# lightampSMT.net
KiCad netlist of a schematic drawn in EAGLE
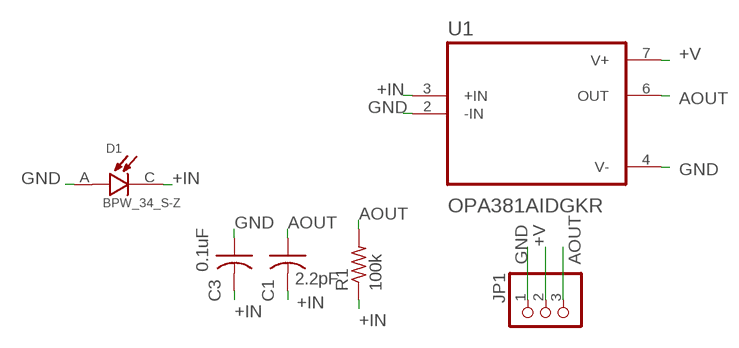
[diagram p0: schematic, sheet 1]

(export (version "E")
  (design (tool "Eeschema 10.0.6"))
  (components
    (comp (ref "C1")
      (value "2.2pF")
      (footprint "eagle-import:C0603K")
      (libsource (lib "eagle-import") (part "C-USC0603K"))
    )
    (comp (ref "C3")
      (value "0.1uF")
      (footprint "eagle-import:C0603K")
      (libsource (lib "eagle-import") (part "C-USC0603K"))
    )
    (comp (ref "D1")
      (value "BPW_34_S-Z")
      (footprint "eagle-import:DIO_BPW_34_S-Z")
      (fields (field (name "MF") "OSRAM Opto") (field (name "MP") "BPW 34 S-Z"))
      (libsource (lib "eagle-import") (part "BPW_34_S-Z"))
    )
    (comp (ref "JP1")
      (value "PINHD-1X3")
      (footprint "eagle-import:1X03")
      (libsource (lib "eagle-import") (part "PINHD-1X3"))
    )
    (comp (ref "R1")
      (value "100k")
      (footprint "eagle-import:R0603")
      (libsource (lib "eagle-import") (part "R-US_R0603"))
    )
    (comp (ref "U1")
      (value "OPA381AIDGKR")
      (footprint "eagle-import:SOP65P490X110-8N")
      (fields (field (name "MF") "Texas Instruments"))
      (libsource (lib "eagle-import") (part "OPA381AIDGKR"))
    )
  )
  (nets
    (net (code "1") (name "/+IN") (class "Default")
      (node (ref "C1") (pin "2") (pinfunction "2_2") (pintype "passive"))
      (node (ref "C3") (pin "2") (pinfunction "2_2") (pintype "passive"))
      (node (ref "D1") (pin "C") (pinfunction "C_C") (pintype "passive"))
      (node (ref "R1") (pin "1") (pinfunction "1_1") (pintype "passive"))
      (node (ref "U1") (pin "3") (pinfunction "+IN_3") (pintype "input"))
    )
    (net (code "2") (name "/+V") (class "Default")
      (node (ref "JP1") (pin "2") (pinfunction "2_2") (pintype "passive"))
      (node (ref "U1") (pin "7") (pinfunction "V+_7") (pintype "power_in"))
    )
    (net (code "3") (name "/AOUT") (class "Default")
      (node (ref "C1") (pin "1") (pinfunction "1_1") (pintype "passive"))
      (node (ref "JP1") (pin "3") (pinfunction "3_3") (pintype "passive"))
      (node (ref "R1") (pin "2") (pinfunction "2_2") (pintype "passive"))
      (node (ref "U1") (pin "6") (pinfunction "OUT_6") (pintype "output"))
    )
    (net (code "4") (name "/GND") (class "Default")
      (node (ref "C3") (pin "1") (pinfunction "1_1") (pintype "passive"))
      (node (ref "D1") (pin "A") (pinfunction "A_A") (pintype "passive"))
      (node (ref "JP1") (pin "1") (pinfunction "1_1") (pintype "passive"))
      (node (ref "U1") (pin "2") (pinfunction "-IN_2") (pintype "input"))
      (node (ref "U1") (pin "4") (pinfunction "V-_4") (pintype "power_in"))
    )
  )
)
